# Signal_Conditioning_2.net
KiCad netlist of a schematic drawn in Altium Designer
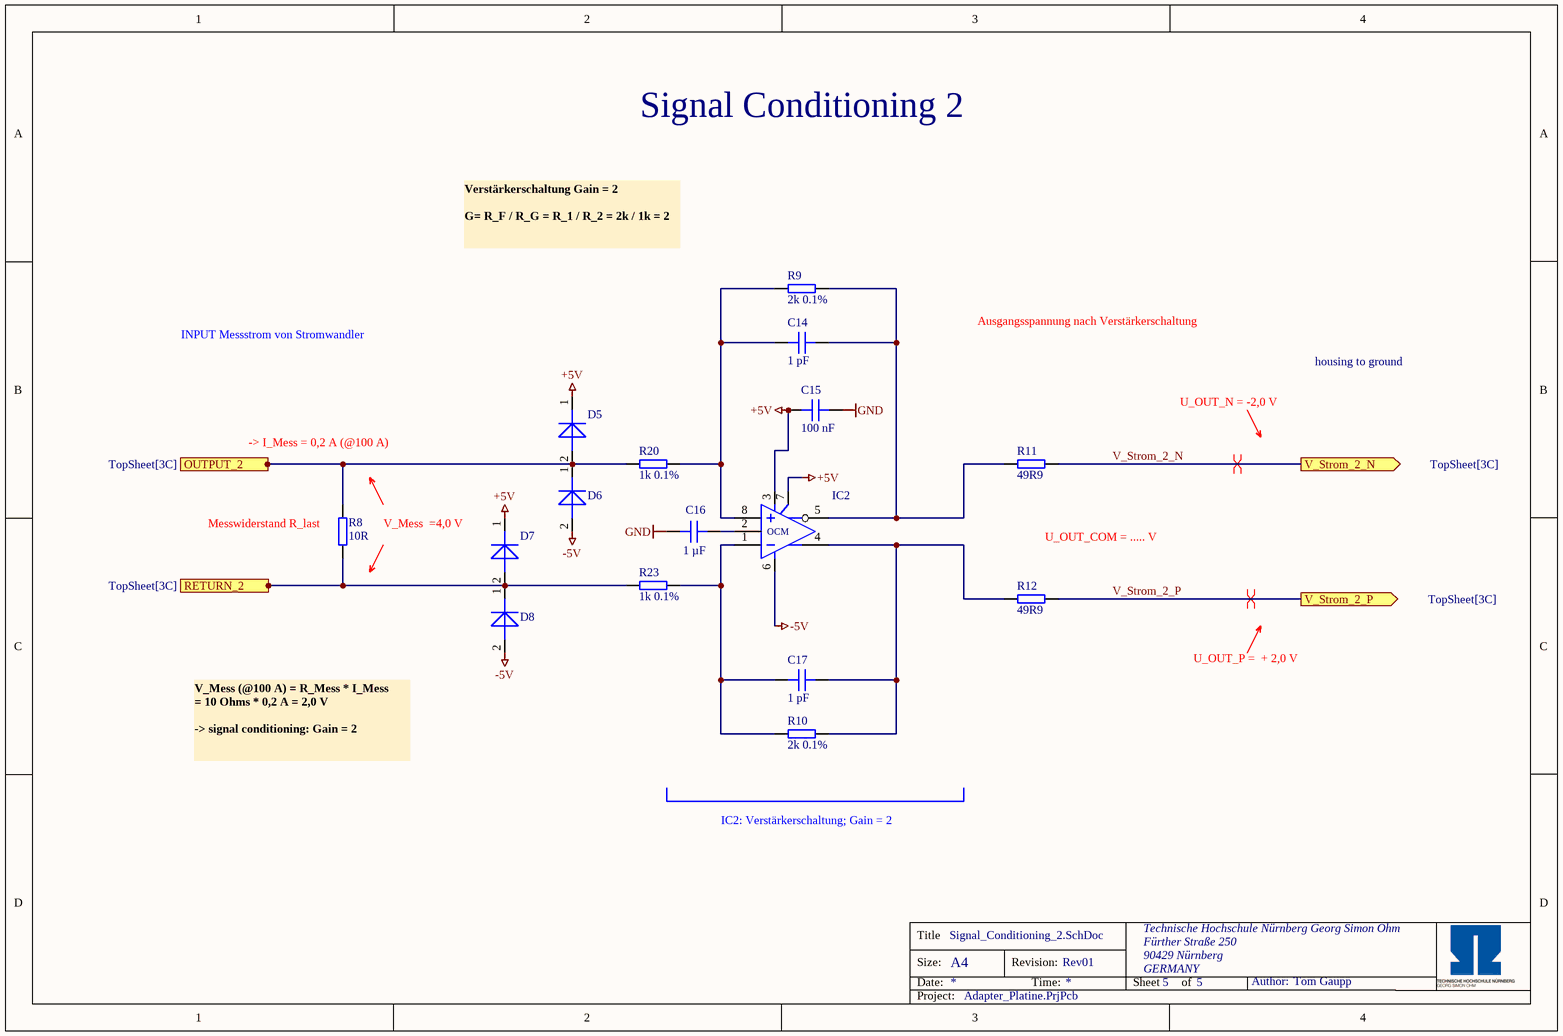
[diagram p0: Signal_Conditioning_2.SchDoc]

(export (version "E")
  (design (tool "Eeschema 10.0.6"))
  (components
    (comp (ref "C14")
      (value "1 pF")
      (footprint "C_0603")
      (description "Multilayer Ceramic Capacitors MLCC - SMD/SMT 50V 1pF C0G 0603 +/-.1pF")
      (fields
        (field (name "MANUFACTURER PART NUMBER") "KGM15ACG1H1R0BT")
        (field (name "MANUFACTURER") "KYOCERA AVX")
        (field (name "CREATED FROM") "TGaupp")
      )
      (libsource (lib "user") (part "Capacitor"))
    )
    (comp (ref "C15")
      (value "100 nF")
      (footprint "C_0603")
      (description "Capacitor 0603, 6.3 VDC, 100 nF, X5R")
      (fields
        (field (name "MANUFACTURER PART NUMBER") "C0603C104K9PACTU")
        (field (name "MANUFACTURER") "KEMET")
        (field (name "CREATED FROM") "MGremer")
      )
      (libsource (lib "user") (part "Capacitor"))
    )
    (comp (ref "C16")
      (value "1 µF")
      (footprint "C_0603")
      (description "50V 1uF X5R ±10% 0603  Multilayer Ceramic Capacitors MLCC - SMD/SMT ROHS")
      (fields
        (field (name "MANUFACTURER") "Samsung Electro-Mechanics")
        (field (name "MANUFACTURER PART NUMBER") "CL10A105KB8NNNC")
        (field (name "CREATED FROM") "MGremer")
      )
      (libsource (lib "user") (part "Capacitor"))
    )
    (comp (ref "C17")
      (value "1 pF")
      (footprint "C_0603")
      (description "Multilayer Ceramic Capacitors MLCC - SMD/SMT 50V 1pF C0G 0603 +/-.1pF")
      (fields
        (field (name "MANUFACTURER PART NUMBER") "KGM15ACG1H1R0BT")
        (field (name "MANUFACTURER") "KYOCERA AVX")
        (field (name "CREATED FROM") "TGaupp")
      )
      (libsource (lib "user") (part "Capacitor"))
    )
    (comp (ref "D5")
      (value "1SS356VMFHTE-17")
      (footprint "eigene_lib_alt:1SS356VMFHTE17")
      (description "Diode")
      (fields (field (name "MOUSER PART NUMBER") "755-1SS356VMFHTE-17"))
      (libsource (lib "SamacSys") (part "1SS356VMFHTE-17"))
    )
    (comp (ref "D6")
      (value "1SS356VMFHTE-17")
      (footprint "eigene_lib_alt:1SS356VMFHTE17")
      (description "Diode")
      (fields (field (name "MOUSER PART NUMBER") "755-1SS356VMFHTE-17"))
      (libsource (lib "SamacSys") (part "1SS356VMFHTE-17"))
    )
    (comp (ref "D7")
      (value "1SS356VMFHTE-17")
      (footprint "eigene_lib_alt:1SS356VMFHTE17")
      (description "Diode")
      (fields (field (name "MOUSER PART NUMBER") "755-1SS356VMFHTE-17"))
      (libsource (lib "SamacSys") (part "1SS356VMFHTE-17"))
    )
    (comp (ref "D8")
      (value "1SS356VMFHTE-17")
      (footprint "eigene_lib_alt:1SS356VMFHTE17")
      (description "Diode")
      (fields (field (name "MOUSER PART NUMBER") "755-1SS356VMFHTE-17"))
      (libsource (lib "SamacSys") (part "1SS356VMFHTE-17"))
    )
    (comp (ref "IC2")
      (value "ADA4940-1ARZ-R7")
      (footprint "SOIC-8-N")
      (description "Differential ADC Driver")
      (fields (field (name "MANUFACTURER") "Analog Devices") (field (name "CREATED FROM") "MGremer"))
      (libsource (lib "user") (part "ADA4940-1ARZ"))
    )
    (comp (ref "R8")
      (value "10R")
      (footprint "RES 1206_3216")
      (description "SMD 10 ohm 0.5% 0.5W")
      (fields
        (field (name "MANUFACTURER PART NUMBER") "SG73G2BTTD10R0D")
        (field (name "MANUFACTURER") "KOA Speer")
        (field (name "CREATED FROM") "TGaupp")
      )
      (libsource (lib "user") (part "Resistor"))
    )
    (comp (ref "R9")
      (value "2k 0.1%")
      (footprint "RES 1206_3216")
      (description "SMD resistor 2Kohms .1% 400mW 25ppm")
      (fields
        (field (name "MANUFACTURER PART NUMBER") "TNPW12062K00BEEA")
        (field (name "MANUFACTURER") "Vishay")
        (field (name "CREATED FROM") "TGaupp")
      )
      (libsource (lib "user") (part "Resistor"))
    )
    (comp (ref "R10")
      (value "2k 0.1%")
      (footprint "RES 1206_3216")
      (description "SMD resistor 2Kohms .1% 400mW 25ppm")
      (fields
        (field (name "MANUFACTURER PART NUMBER") "TNPW12062K00BEEA")
        (field (name "MANUFACTURER") "Vishay")
        (field (name "CREATED FROM") "TGaupp")
      )
      (libsource (lib "user") (part "Resistor"))
    )
    (comp (ref "R11")
      (value "49R9")
      (footprint "RES 0603_1608")
      (description "100mW Thick Film Resistors ±100ppm/℃ ±1% 49.9Ω 0603 Chip Resistor - Surface Mount ROHS")
      (fields
        (field (name "MANUFACTURER PART NUMBER") "RC0603FR-0749R9L")
        (field (name "MANUFACTURER") "YAGEO")
        (field (name "CREATED FROM") "AGeiger")
      )
      (libsource (lib "user") (part "Resistor"))
    )
    (comp (ref "R12")
      (value "49R9")
      (footprint "RES 0603_1608")
      (description "100mW Thick Film Resistors ±100ppm/℃ ±1% 49.9Ω 0603 Chip Resistor - Surface Mount ROHS")
      (fields
        (field (name "MANUFACTURER PART NUMBER") "RC0603FR-0749R9L")
        (field (name "MANUFACTURER") "YAGEO")
        (field (name "CREATED FROM") "AGeiger")
      )
      (libsource (lib "user") (part "Resistor"))
    )
    (comp (ref "R20")
      (value "1k 0.1%")
      (footprint "RES 1206_3216")
      (description "SMD resistor 1/4W 1.0Kohm 0.1% 25ppm")
      (fields
        (field (name "MANUFACTURER PART NUMBER") "ERA-8AEB102V")
        (field (name "MANUFACTURER") "Panasonic")
        (field (name "CREATED FROM") "TGaupp")
      )
      (libsource (lib "user") (part "Resistor"))
    )
    (comp (ref "R23")
      (value "1k 0.1%")
      (footprint "RES 1206_3216")
      (description "SMD resistor 1/4W 1.0Kohm 0.1% 25ppm")
      (fields
        (field (name "MANUFACTURER PART NUMBER") "ERA-8AEB102V")
        (field (name "MANUFACTURER") "Panasonic")
        (field (name "CREATED FROM") "TGaupp")
      )
      (libsource (lib "user") (part "Resistor"))
    )
  )
  (nets
    (net (code "1") (name "+5V") (class "Default")
      (node (ref "C15") (pin "1") (pinfunction "1_1") (pintype "passive"))
      (node (ref "D5") (pin "1") (pinfunction "K_1") (pintype "passive"))
      (node (ref "D7") (pin "1") (pinfunction "K_1") (pintype "passive"))
      (node (ref "IC2") (pin "3") (pinfunction "V+_3") (pintype "passive"))
      (node (ref "IC2") (pin "7") (pinfunction "EN_7") (pintype "passive"))
    )
    (net (code "2") (name "-5V") (class "Default")
      (node (ref "D6") (pin "2") (pinfunction "A_2") (pintype "passive"))
      (node (ref "D8") (pin "2") (pinfunction "A_2") (pintype "passive"))
      (node (ref "IC2") (pin "6") (pinfunction "V-_6") (pintype "passive"))
    )
    (net (code "3") (name "/OUTPUT_2") (class "Default")
      (node (ref "D5") (pin "2") (pinfunction "A_2") (pintype "passive"))
      (node (ref "D6") (pin "1") (pinfunction "K_1") (pintype "passive"))
      (node (ref "R20") (pin "1") (pinfunction "1_1") (pintype "passive"))
      (node (ref "R8") (pin "2") (pinfunction "2_2") (pintype "passive"))
    )
    (net (code "4") (name "/RETURN_2") (class "Default")
      (node (ref "D7") (pin "2") (pinfunction "A_2") (pintype "passive"))
      (node (ref "D8") (pin "1") (pinfunction "K_1") (pintype "passive"))
      (node (ref "R23") (pin "1") (pinfunction "1_1") (pintype "passive"))
      (node (ref "R8") (pin "1") (pinfunction "1_1") (pintype "passive"))
    )
    (net (code "5") (name "/V_Strom_2_N") (class "Default")
      (node (ref "R11") (pin "2") (pinfunction "2_2") (pintype "passive"))
    )
    (net (code "6") (name "/V_Strom_2_P") (class "Default")
      (node (ref "R12") (pin "2") (pinfunction "2_2") (pintype "passive"))
    )
    (net (code "7") (name "GND") (class "Default")
      (node (ref "C15") (pin "2") (pinfunction "2_2") (pintype "passive"))
      (node (ref "C16") (pin "1") (pinfunction "1_1") (pintype "passive"))
    )
    (net (code "8") (name "Net-(C14-Pad2)") (class "Default")
      (node (ref "C14") (pin "2") (pinfunction "2_2") (pintype "passive"))
      (node (ref "IC2") (pin "5") (pinfunction "Out_5") (pintype "passive"))
      (node (ref "R11") (pin "1") (pinfunction "1_1") (pintype "passive"))
      (node (ref "R9") (pin "2") (pinfunction "2_2") (pintype "passive"))
    )
    (net (code "9") (name "Net-(C17-Pad2)") (class "Default")
      (node (ref "C17") (pin "2") (pinfunction "2_2") (pintype "passive"))
      (node (ref "IC2") (pin "4") (pinfunction "Out_4") (pintype "passive"))
      (node (ref "R10") (pin "2") (pinfunction "2_2") (pintype "passive"))
      (node (ref "R12") (pin "1") (pinfunction "1_1") (pintype "passive"))
    )
    (net (code "10") (name "Net-(IC2-+)") (class "Default")
      (node (ref "C14") (pin "1") (pinfunction "1_1") (pintype "passive"))
      (node (ref "IC2") (pin "8") (pinfunction "+_8") (pintype "passive"))
      (node (ref "R20") (pin "2") (pinfunction "2_2") (pintype "passive"))
      (node (ref "R9") (pin "1") (pinfunction "1_1") (pintype "passive"))
    )
    (net (code "11") (name "Net-(IC2--)") (class "Default")
      (node (ref "C17") (pin "1") (pinfunction "1_1") (pintype "passive"))
      (node (ref "IC2") (pin "1") (pinfunction "-_1") (pintype "passive"))
      (node (ref "R10") (pin "1") (pinfunction "1_1") (pintype "passive"))
      (node (ref "R23") (pin "2") (pinfunction "2_2") (pintype "passive"))
    )
    (net (code "12") (name "Net-(IC2-OCM)") (class "Default")
      (node (ref "C16") (pin "2") (pinfunction "2_2") (pintype "passive"))
      (node (ref "IC2") (pin "2") (pinfunction "OCM_2") (pintype "passive"))
    )
  )
)
